# IO_Combo_Keyboard_Mouse.net
KiCad netlist of a schematic drawn in Altium Designer
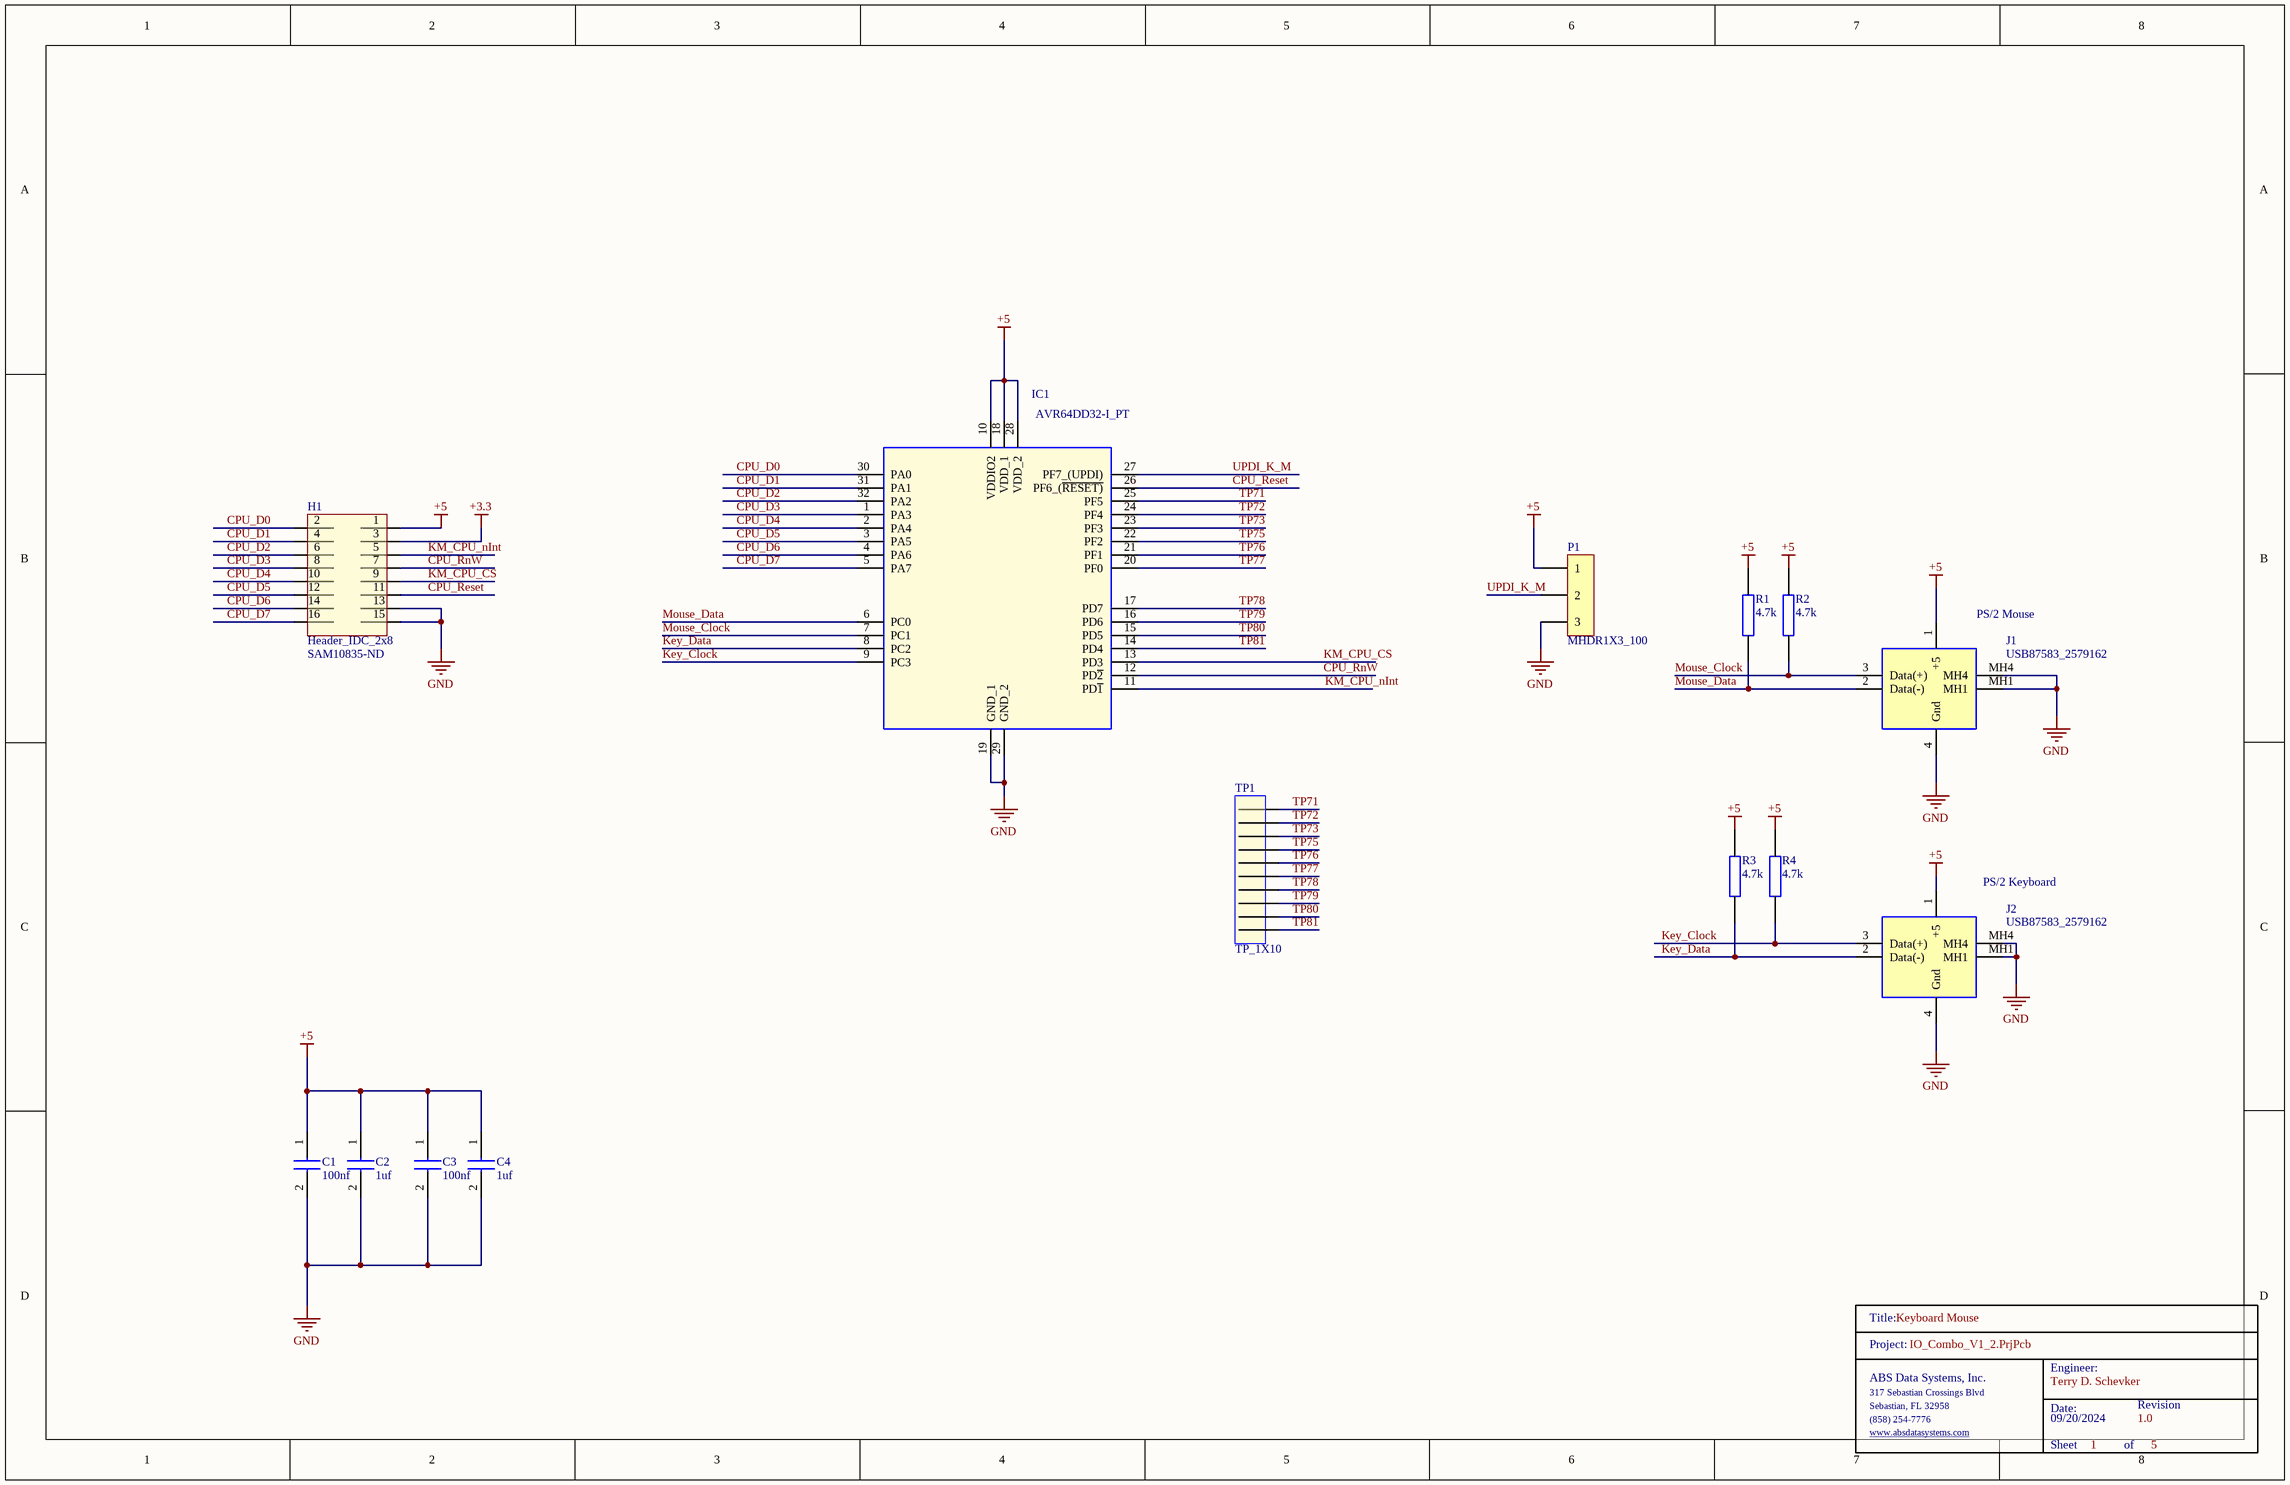
[diagram p0: IO_Combo_Keyboard_Mouse.SchDoc]

(export (version "E")
  (design (tool "Eeschema 10.0.6"))
  (components
    (comp (ref "C1")
      (value "100nf")
      (footprint "0603")
      (description "Samsung Electro-Mechanics 0603 100nf")
      (libsource (lib "Capacitors") (part "CL10B104JB8NNNC"))
    )
    (comp (ref "C2")
      (value "1uf")
      (footprint "0603")
      (description "Samsung Electro-Mechanics 0603 1uf")
      (libsource (lib "Capacitors") (part "CL10B105KA8NNNL"))
    )
    (comp (ref "C3")
      (value "100nf")
      (footprint "0603")
      (description "Samsung Electro-Mechanics 0603 100nf")
      (libsource (lib "Capacitors") (part "CL10B104JB8NNNC"))
    )
    (comp (ref "C4")
      (value "1uf")
      (footprint "0603")
      (description "Samsung Electro-Mechanics 0603 1uf")
      (libsource (lib "Capacitors") (part "CL10B105KA8NNNL"))
    )
    (comp (ref "H1")
      (value "Header_IDC_2x8")
      (footprint "HEADER16")
      (description "16 Pin 2x8 Through Hold IDC Connector")
      (fields
        (field (name "MANUFACTURER") "Samtec")
        (field (name "MANUFACTURER PART NUMBER") "TST-108-01-G-D")
        (field (name "SUPPLIER PART NUMBER 1") "SAM10835-ND")
      )
      (libsource (lib "Misc") (part "Header_IDC_2x8"))
    )
    (comp (ref "IC1")
      (value "AVR64DD32-I_PT")
      (footprint "CPU_Memory:QFP80P900X900X120-32N")
      (description "Integrated Circuit")
      (fields (field (name "MANUFACTURER_PART_NUMBER") "AVR64DD32-I/PT ¦ MULTI-VOLTAGE I/O"))
      (libsource (lib "CPU_Memory") (part "AVR64DD32-I_PT"))
    )
    (comp (ref "J1")
      (value "USB87583_2579162")
      (footprint "87583-2579162")
      (description "USB Connectors USB A Plug, SMT, R/A, GF, With Kinked shell stakes and posts, T&R")
      (fields
        (field (name "MOUSER PART NUMBER") "640-USB1061-GF-L-A")
        (field (name "MANUFACTURER_PART_NUMBER") "USB1061-GF-L-A")
      )
      (libsource (lib "Connectors") (part "USB87583_2579162"))
    )
    (comp (ref "J2")
      (value "USB87583_2579162")
      (footprint "87583-2579162")
      (description "USB Connectors USB A Plug, SMT, R/A, GF, With Kinked shell stakes and posts, T&R")
      (fields
        (field (name "MOUSER PART NUMBER") "640-USB1061-GF-L-A")
        (field (name "MANUFACTURER_PART_NUMBER") "USB1061-GF-L-A")
      )
      (libsource (lib "Connectors") (part "USB87583_2579162"))
    )
    (comp (ref "P1")
      (value "MHDR1X3_100")
      (footprint "MHDR1X3_100")
      (description "Header, 3-Pin")
      (fields (field (name "PUBLISHER") "Altium Limited"))
      (libsource (lib "Connectors") (part "MHDR1X3_100"))
    )
    (comp (ref "R1")
      (value "4.7k")
      (footprint "0603")
      (description "YAGEO 0603 4.7k")
      (fields
        (field (name "MOUSER PART NUMBER") "603-RC0603JR-070RL")
        (field (name "MANUFACTURER_PART_NUMBER") "RC0603JR-070RL")
      )
      (libsource (lib "Resistors") (part "RC0603FR-104K7L"))
    )
    (comp (ref "R2")
      (value "4.7k")
      (footprint "0603")
      (description "YAGEO 0603 4.7k")
      (fields
        (field (name "MOUSER PART NUMBER") "603-RC0603JR-070RL")
        (field (name "MANUFACTURER_PART_NUMBER") "RC0603JR-070RL")
      )
      (libsource (lib "Resistors") (part "RC0603FR-104K7L"))
    )
    (comp (ref "R3")
      (value "4.7k")
      (footprint "0603")
      (description "YAGEO 0603 4.7k")
      (fields
        (field (name "MOUSER PART NUMBER") "603-RC0603JR-070RL")
        (field (name "MANUFACTURER_PART_NUMBER") "RC0603JR-070RL")
      )
      (libsource (lib "Resistors") (part "RC0603FR-104K7L"))
    )
    (comp (ref "R4")
      (value "4.7k")
      (footprint "0603")
      (description "YAGEO 0603 4.7k")
      (fields
        (field (name "MOUSER PART NUMBER") "603-RC0603JR-070RL")
        (field (name "MANUFACTURER_PART_NUMBER") "RC0603JR-070RL")
      )
      (libsource (lib "Resistors") (part "RC0603FR-104K7L"))
    )
    (comp (ref "TP1")
      (value "TP_1X10")
      (footprint "TP_1X10")
      (fields
        (field (name "MANUFACTURER") "Samtec")
        (field (name "MANUFACTURER PART NUMBER") "TST-105-01-G-D")
      )
      (libsource (lib "Misc") (part "TP_1X10"))
    )
  )
  (nets
    (net (code "1") (name "+3.3") (class "Default")
      (node (ref "H1") (pin "3") (pinfunction "3_3") (pintype "passive"))
    )
    (net (code "2") (name "+5") (class "Default")
      (node (ref "C1") (pin "1") (pinfunction "1_1") (pintype "passive"))
      (node (ref "C2") (pin "1") (pinfunction "1_1") (pintype "passive"))
      (node (ref "C3") (pin "1") (pinfunction "1_1") (pintype "passive"))
      (node (ref "C4") (pin "1") (pinfunction "1_1") (pintype "passive"))
      (node (ref "H1") (pin "1") (pinfunction "1_1") (pintype "passive"))
      (node (ref "IC1") (pin "10") (pinfunction "VDDIO2_10") (pintype "passive"))
      (node (ref "IC1") (pin "18") (pinfunction "VDD_1_18") (pintype "passive"))
      (node (ref "IC1") (pin "28") (pinfunction "VDD_2_28") (pintype "passive"))
      (node (ref "J1") (pin "1") (pinfunction "+5_1") (pintype "passive"))
      (node (ref "J2") (pin "1") (pinfunction "+5_1") (pintype "passive"))
      (node (ref "P1") (pin "1") (pinfunction "1_1") (pintype "passive"))
      (node (ref "R1") (pin "1") (pinfunction "1_1") (pintype "passive"))
      (node (ref "R2") (pin "1") (pinfunction "1_1") (pintype "passive"))
      (node (ref "R3") (pin "1") (pinfunction "1_1") (pintype "passive"))
      (node (ref "R4") (pin "1") (pinfunction "1_1") (pintype "passive"))
    )
    (net (code "3") (name "/CPU_D0") (class "Default")
      (node (ref "H1") (pin "2") (pinfunction "2_2") (pintype "passive"))
      (node (ref "IC1") (pin "30") (pinfunction "PA0_30") (pintype "passive"))
    )
    (net (code "4") (name "/CPU_D1") (class "Default")
      (node (ref "H1") (pin "4") (pinfunction "4_4") (pintype "passive"))
      (node (ref "IC1") (pin "31") (pinfunction "PA1_31") (pintype "passive"))
    )
    (net (code "5") (name "/CPU_D2") (class "Default")
      (node (ref "H1") (pin "6") (pinfunction "6_6") (pintype "passive"))
      (node (ref "IC1") (pin "32") (pinfunction "PA2_32") (pintype "passive"))
    )
    (net (code "6") (name "/CPU_D3") (class "Default")
      (node (ref "H1") (pin "8") (pinfunction "8_8") (pintype "passive"))
      (node (ref "IC1") (pin "1") (pinfunction "PA3_1") (pintype "passive"))
    )
    (net (code "7") (name "/CPU_D4") (class "Default")
      (node (ref "H1") (pin "10") (pinfunction "10_10") (pintype "passive"))
      (node (ref "IC1") (pin "2") (pinfunction "PA4_2") (pintype "passive"))
    )
    (net (code "8") (name "/CPU_D5") (class "Default")
      (node (ref "H1") (pin "12") (pinfunction "12_12") (pintype "passive"))
      (node (ref "IC1") (pin "3") (pinfunction "PA5_3") (pintype "passive"))
    )
    (net (code "9") (name "/CPU_D6") (class "Default")
      (node (ref "H1") (pin "14") (pinfunction "14_14") (pintype "passive"))
      (node (ref "IC1") (pin "4") (pinfunction "PA6_4") (pintype "passive"))
    )
    (net (code "10") (name "/CPU_D7") (class "Default")
      (node (ref "H1") (pin "16") (pinfunction "16_16") (pintype "passive"))
      (node (ref "IC1") (pin "5") (pinfunction "PA7_5") (pintype "passive"))
    )
    (net (code "11") (name "/CPU_Reset") (class "Default")
      (node (ref "H1") (pin "11") (pinfunction "11_11") (pintype "passive"))
      (node (ref "IC1") (pin "26") (pinfunction "PF6_(~{RESET)}_26") (pintype "passive"))
    )
    (net (code "12") (name "/CPU_RnW") (class "Default")
      (node (ref "H1") (pin "7") (pinfunction "7_7") (pintype "passive"))
      (node (ref "IC1") (pin "12") (pinfunction "PD~{2}_12") (pintype "passive"))
    )
    (net (code "13") (name "/KM_CPU_CS") (class "Default")
      (node (ref "H1") (pin "9") (pinfunction "9_9") (pintype "passive"))
      (node (ref "IC1") (pin "13") (pinfunction "PD3_13") (pintype "passive"))
    )
    (net (code "14") (name "/KM_CPU_nInt") (class "Default")
      (node (ref "H1") (pin "5") (pinfunction "5_5") (pintype "passive"))
      (node (ref "IC1") (pin "11") (pinfunction "PD~{1}_11") (pintype "passive"))
    )
    (net (code "15") (name "/Key_Clock") (class "Default")
      (node (ref "IC1") (pin "9") (pinfunction "PC3_9") (pintype "passive"))
      (node (ref "J2") (pin "3") (pinfunction "Data(+)_3") (pintype "passive"))
      (node (ref "R4") (pin "2") (pinfunction "2_2") (pintype "passive"))
    )
    (net (code "16") (name "/Key_Data") (class "Default")
      (node (ref "IC1") (pin "8") (pinfunction "PC2_8") (pintype "passive"))
      (node (ref "J2") (pin "2") (pinfunction "Data(-)_2") (pintype "passive"))
      (node (ref "R3") (pin "2") (pinfunction "2_2") (pintype "passive"))
    )
    (net (code "17") (name "/Mouse_Clock") (class "Default")
      (node (ref "IC1") (pin "7") (pinfunction "PC1_7") (pintype "passive"))
      (node (ref "J1") (pin "3") (pinfunction "Data(+)_3") (pintype "passive"))
      (node (ref "R2") (pin "2") (pinfunction "2_2") (pintype "passive"))
    )
    (net (code "18") (name "/Mouse_Data") (class "Default")
      (node (ref "IC1") (pin "6") (pinfunction "PC0_6") (pintype "passive"))
      (node (ref "J1") (pin "2") (pinfunction "Data(-)_2") (pintype "passive"))
      (node (ref "R1") (pin "2") (pinfunction "2_2") (pintype "passive"))
    )
    (net (code "19") (name "/TP71") (class "Default")
      (node (ref "IC1") (pin "25") (pinfunction "PF5_25") (pintype "passive"))
      (node (ref "TP1") (pin "1") (pinfunction "1_1") (pintype "passive"))
    )
    (net (code "20") (name "/TP72") (class "Default")
      (node (ref "IC1") (pin "24") (pinfunction "PF4_24") (pintype "passive"))
      (node (ref "TP1") (pin "2") (pinfunction "2_2") (pintype "passive"))
    )
    (net (code "21") (name "/TP73") (class "Default")
      (node (ref "IC1") (pin "23") (pinfunction "PF3_23") (pintype "passive"))
      (node (ref "TP1") (pin "3") (pinfunction "3_3") (pintype "passive"))
    )
    (net (code "22") (name "/TP75") (class "Default")
      (node (ref "IC1") (pin "22") (pinfunction "PF2_22") (pintype "passive"))
      (node (ref "TP1") (pin "4") (pinfunction "4_4") (pintype "passive"))
    )
    (net (code "23") (name "/TP76") (class "Default")
      (node (ref "IC1") (pin "21") (pinfunction "PF1_21") (pintype "passive"))
      (node (ref "TP1") (pin "5") (pinfunction "5_5") (pintype "passive"))
    )
    (net (code "24") (name "/TP77") (class "Default")
      (node (ref "IC1") (pin "20") (pinfunction "PF0_20") (pintype "passive"))
      (node (ref "TP1") (pin "6") (pinfunction "6_6") (pintype "passive"))
    )
    (net (code "25") (name "/TP78") (class "Default")
      (node (ref "IC1") (pin "17") (pinfunction "PD7_17") (pintype "passive"))
      (node (ref "TP1") (pin "7") (pinfunction "7_7") (pintype "passive"))
    )
    (net (code "26") (name "/TP79") (class "Default")
      (node (ref "IC1") (pin "16") (pinfunction "PD6_16") (pintype "passive"))
      (node (ref "TP1") (pin "8") (pinfunction "8_8") (pintype "passive"))
    )
    (net (code "27") (name "/TP80") (class "Default")
      (node (ref "IC1") (pin "15") (pinfunction "PD5_15") (pintype "passive"))
      (node (ref "TP1") (pin "9") (pinfunction "9_9") (pintype "passive"))
    )
    (net (code "28") (name "/TP81") (class "Default")
      (node (ref "IC1") (pin "14") (pinfunction "PD4_14") (pintype "passive"))
      (node (ref "TP1") (pin "10") (pinfunction "10_10") (pintype "passive"))
    )
    (net (code "29") (name "/UPDI_K_M") (class "Default")
      (node (ref "IC1") (pin "27") (pinfunction "PF7_(UPDI)_27") (pintype "passive"))
      (node (ref "P1") (pin "2") (pinfunction "2_2") (pintype "passive"))
    )
    (net (code "30") (name "GND") (class "Default")
      (node (ref "C1") (pin "2") (pinfunction "2_2") (pintype "passive"))
      (node (ref "C2") (pin "2") (pinfunction "2_2") (pintype "passive"))
      (node (ref "C3") (pin "2") (pinfunction "2_2") (pintype "passive"))
      (node (ref "C4") (pin "2") (pinfunction "2_2") (pintype "passive"))
      (node (ref "H1") (pin "13") (pinfunction "13_13") (pintype "passive"))
      (node (ref "H1") (pin "15") (pinfunction "15_15") (pintype "passive"))
      (node (ref "IC1") (pin "19") (pinfunction "GND_1_19") (pintype "passive"))
      (node (ref "IC1") (pin "29") (pinfunction "GND_2_29") (pintype "passive"))
      (node (ref "J1") (pin "4") (pinfunction "Gnd_4") (pintype "passive"))
      (node (ref "J1") (pin "MH1") (pinfunction "MH1_MH1") (pintype "passive"))
      (node (ref "J1") (pin "MH4") (pinfunction "MH4_MH4") (pintype "passive"))
      (node (ref "J2") (pin "4") (pinfunction "Gnd_4") (pintype "passive"))
      (node (ref "J2") (pin "MH1") (pinfunction "MH1_MH1") (pintype "passive"))
      (node (ref "J2") (pin "MH4") (pinfunction "MH4_MH4") (pintype "passive"))
      (node (ref "P1") (pin "3") (pinfunction "3_3") (pintype "passive"))
    )
  )
)
